# BinaryClock_LEDs.net
KiCad netlist of a schematic drawn in Altium Designer
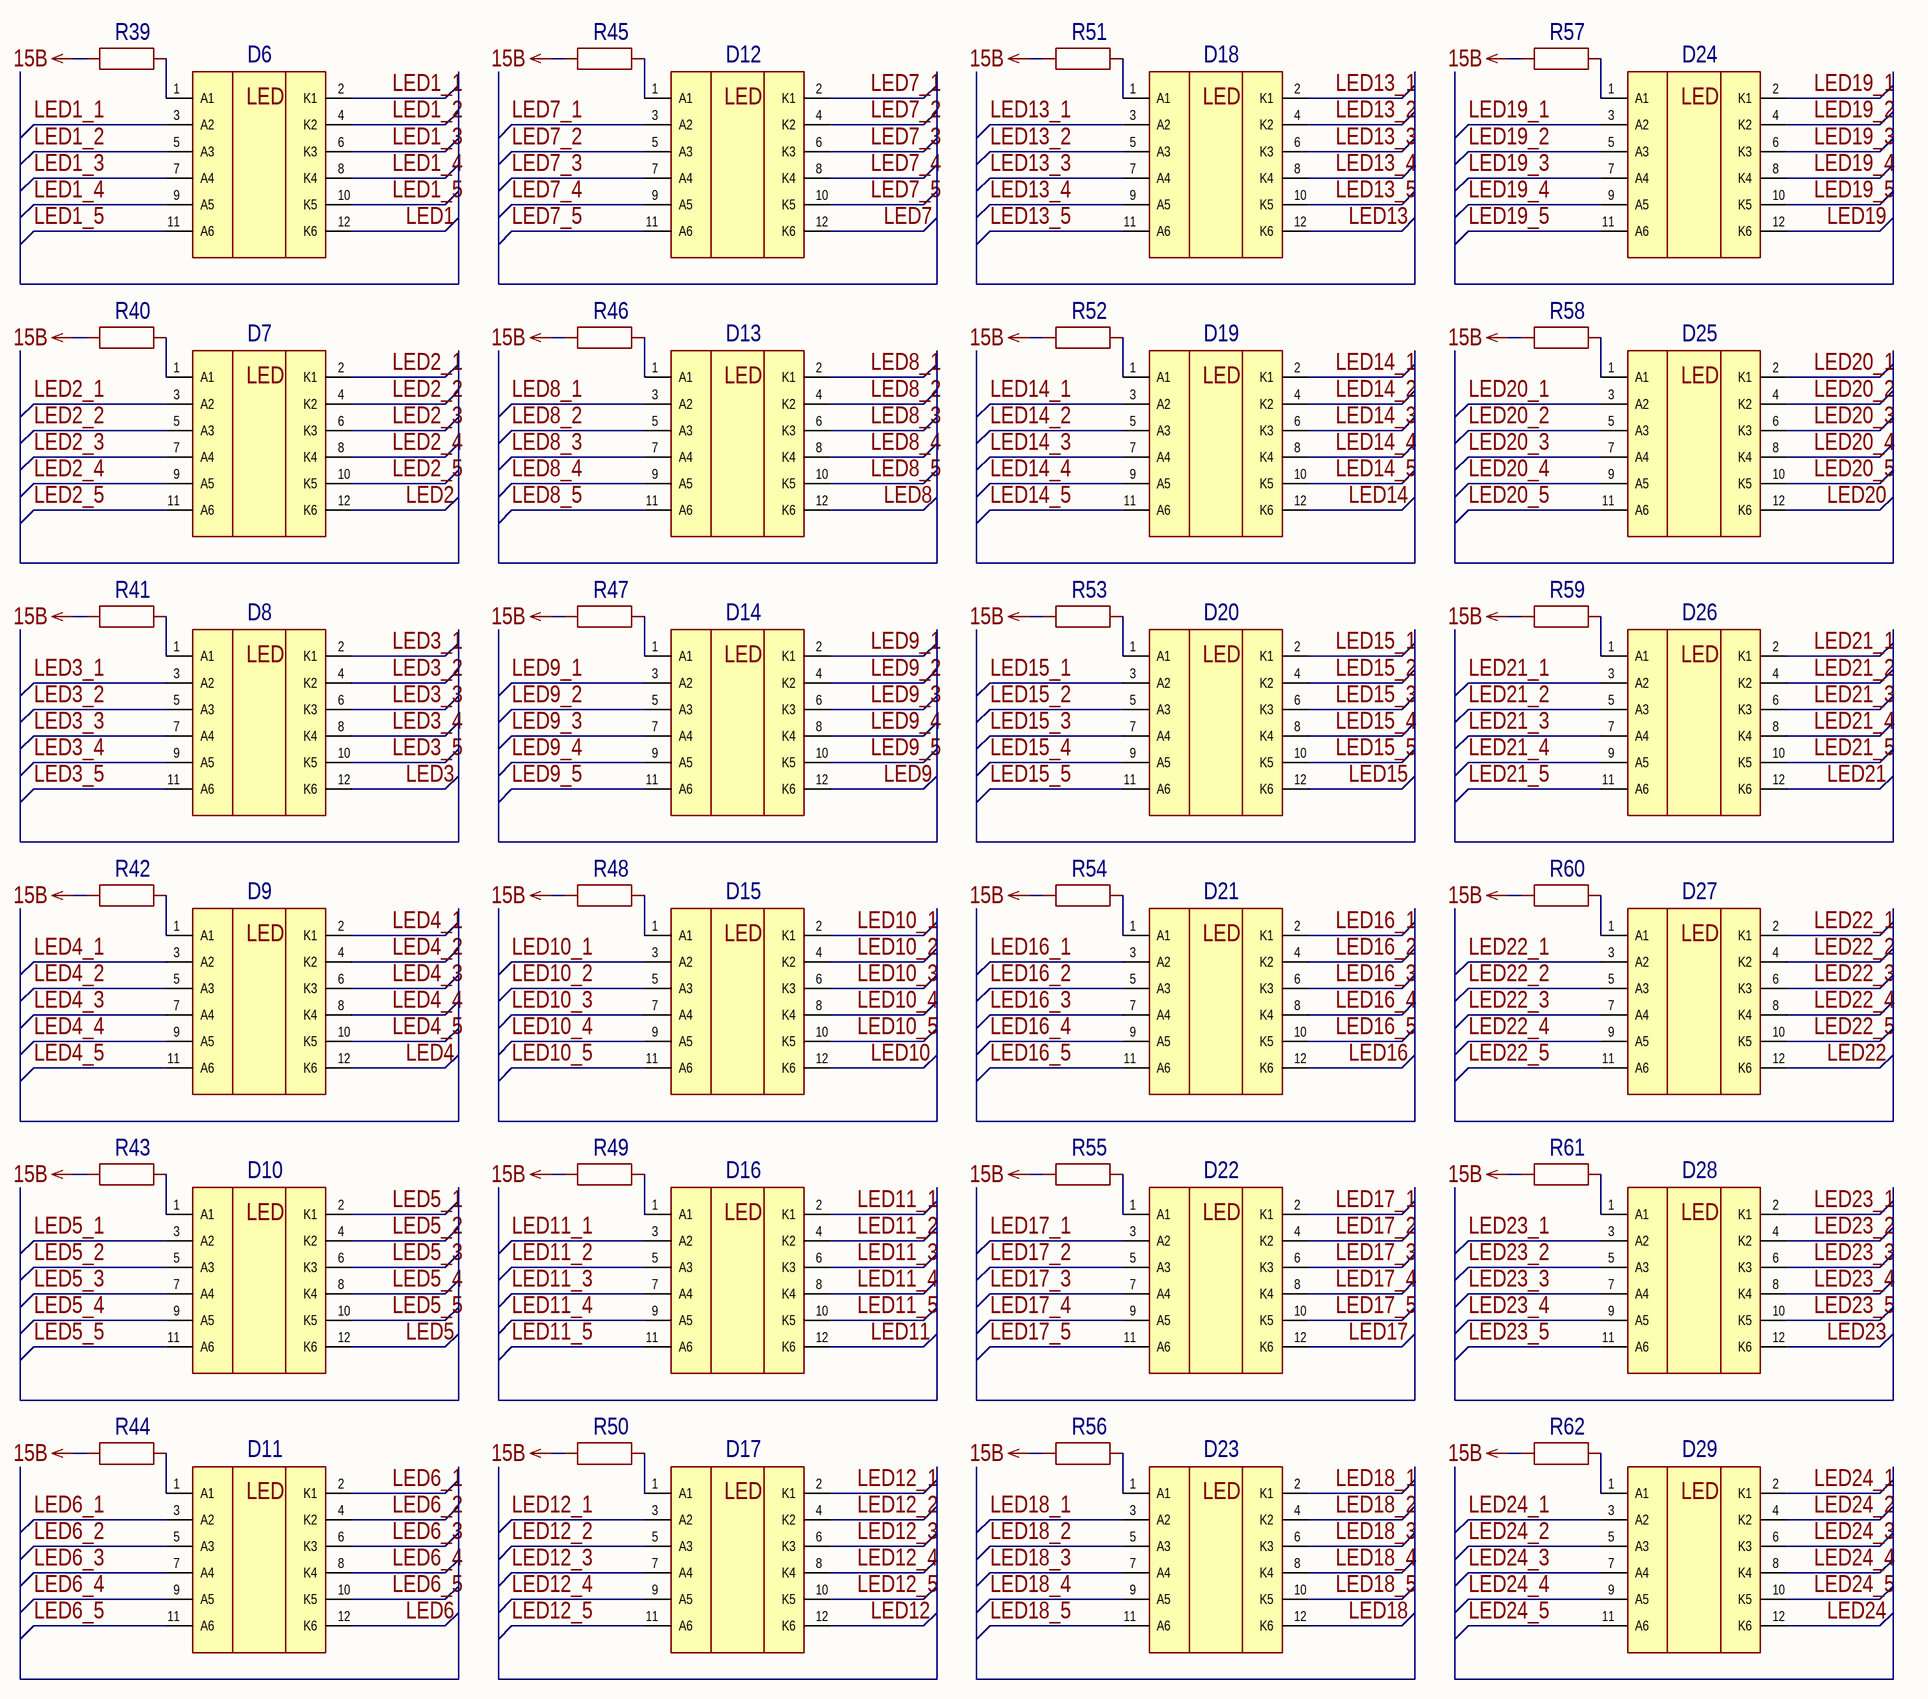
[diagram p0: BinaryClock_LEDs.SchDoc]

(export (version "E")
  (design (tool "Eeschema 10.0.6"))
  (components
    (comp (ref "D6")
      (value "DLA/6ID")
      (footprint "DLA/6ID")
      (description "20mm BIG LAMP")
      (fields (field (name "MANUFACTURER") "Kingbright"))
      (libsource (lib "Devices") (part "DLA"))
    )
    (comp (ref "D7")
      (value "DLA/6ID")
      (footprint "DLA/6ID")
      (description "20mm BIG LAMP")
      (fields (field (name "MANUFACTURER") "Kingbright"))
      (libsource (lib "Devices") (part "DLA"))
    )
    (comp (ref "D8")
      (value "DLA/6ID")
      (footprint "DLA/6ID")
      (description "20mm BIG LAMP")
      (fields (field (name "MANUFACTURER") "Kingbright"))
      (libsource (lib "Devices") (part "DLA"))
    )
    (comp (ref "D9")
      (value "DLA/6ID")
      (footprint "DLA/6ID")
      (description "20mm BIG LAMP")
      (fields (field (name "MANUFACTURER") "Kingbright"))
      (libsource (lib "Devices") (part "DLA"))
    )
    (comp (ref "D10")
      (value "DLA/6ID")
      (footprint "DLA/6ID")
      (description "20mm BIG LAMP")
      (fields (field (name "MANUFACTURER") "Kingbright"))
      (libsource (lib "Devices") (part "DLA"))
    )
    (comp (ref "D11")
      (value "DLA/6ID")
      (footprint "DLA/6ID")
      (description "20mm BIG LAMP")
      (fields (field (name "MANUFACTURER") "Kingbright"))
      (libsource (lib "Devices") (part "DLA"))
    )
    (comp (ref "D12")
      (value "DLA/6ID")
      (footprint "DLA/6ID")
      (description "20mm BIG LAMP")
      (fields (field (name "MANUFACTURER") "Kingbright"))
      (libsource (lib "Devices") (part "DLA"))
    )
    (comp (ref "D13")
      (value "DLA/6ID")
      (footprint "DLA/6ID")
      (description "20mm BIG LAMP")
      (fields (field (name "MANUFACTURER") "Kingbright"))
      (libsource (lib "Devices") (part "DLA"))
    )
    (comp (ref "D14")
      (value "DLA/6YD")
      (footprint "DLA/6YD")
      (description "20mm BIG LAMP")
      (fields (field (name "MANUFACTURER") "Kingbright"))
      (libsource (lib "Devices") (part "DLA"))
    )
    (comp (ref "D15")
      (value "DLA/6YD")
      (footprint "DLA/6YD")
      (description "20mm BIG LAMP")
      (fields (field (name "MANUFACTURER") "Kingbright"))
      (libsource (lib "Devices") (part "DLA"))
    )
    (comp (ref "D16")
      (value "DLA/6YD")
      (footprint "DLA/6YD")
      (description "20mm BIG LAMP")
      (fields (field (name "MANUFACTURER") "Kingbright"))
      (libsource (lib "Devices") (part "DLA"))
    )
    (comp (ref "D17")
      (value "DLA/6YD")
      (footprint "DLA/6YD")
      (description "20mm BIG LAMP")
      (fields (field (name "MANUFACTURER") "Kingbright"))
      (libsource (lib "Devices") (part "DLA"))
    )
    (comp (ref "D18")
      (value "DLA/6YD")
      (footprint "DLA/6YD")
      (description "20mm BIG LAMP")
      (fields (field (name "MANUFACTURER") "Kingbright"))
      (libsource (lib "Devices") (part "DLA"))
    )
    (comp (ref "D19")
      (value "DLA/6YD")
      (footprint "DLA/6YD")
      (description "20mm BIG LAMP")
      (fields (field (name "MANUFACTURER") "Kingbright"))
      (libsource (lib "Devices") (part "DLA"))
    )
    (comp (ref "D20")
      (value "DLA/6YD")
      (footprint "DLA/6YD")
      (description "20mm BIG LAMP")
      (fields (field (name "MANUFACTURER") "Kingbright"))
      (libsource (lib "Devices") (part "DLA"))
    )
    (comp (ref "D21")
      (value "DLA/6YD")
      (footprint "DLA/6YD")
      (description "20mm BIG LAMP")
      (fields (field (name "MANUFACTURER") "Kingbright"))
      (libsource (lib "Devices") (part "DLA"))
    )
    (comp (ref "D22")
      (value "DLA/6GD")
      (footprint "DLA/6GD")
      (description "20mm BIG LAMP")
      (fields (field (name "MANUFACTURER") "Kingbright"))
      (libsource (lib "Devices") (part "DLA"))
    )
    (comp (ref "D23")
      (value "DLA/6GD")
      (footprint "DLA/6GD")
      (description "20mm BIG LAMP")
      (fields (field (name "MANUFACTURER") "Kingbright"))
      (libsource (lib "Devices") (part "DLA"))
    )
    (comp (ref "D24")
      (value "DLA/6GD")
      (footprint "DLA/6GD")
      (description "20mm BIG LAMP")
      (fields (field (name "MANUFACTURER") "Kingbright"))
      (libsource (lib "Devices") (part "DLA"))
    )
    (comp (ref "D25")
      (value "DLA/6GD")
      (footprint "DLA/6GD")
      (description "20mm BIG LAMP")
      (fields (field (name "MANUFACTURER") "Kingbright"))
      (libsource (lib "Devices") (part "DLA"))
    )
    (comp (ref "D26")
      (value "DLA/6GD")
      (footprint "DLA/6GD")
      (description "20mm BIG LAMP")
      (fields (field (name "MANUFACTURER") "Kingbright"))
      (libsource (lib "Devices") (part "DLA"))
    )
    (comp (ref "D27")
      (value "DLA/6GD")
      (footprint "DLA/6GD")
      (description "20mm BIG LAMP")
      (fields (field (name "MANUFACTURER") "Kingbright"))
      (libsource (lib "Devices") (part "DLA"))
    )
    (comp (ref "D28")
      (value "DLA/6GD")
      (footprint "DLA/6GD")
      (description "20mm BIG LAMP")
      (fields (field (name "MANUFACTURER") "Kingbright"))
      (libsource (lib "Devices") (part "DLA"))
    )
    (comp (ref "D29")
      (value "DLA/6GD")
      (footprint "DLA/6GD")
      (description "20mm BIG LAMP")
      (fields (field (name "MANUFACTURER") "Kingbright"))
      (libsource (lib "Devices") (part "DLA"))
    )
    (comp (ref "R39")
      (value "0805±1 %-? кОм")
      (footprint "SMD-0805-RES")
      (description "Resistor")
      (libsource (lib "Passive,Diodes") (part "Res"))
    )
    (comp (ref "R40")
      (value "0805±1 %-? кОм")
      (footprint "SMD-0805-RES")
      (description "Resistor")
      (libsource (lib "Passive,Diodes") (part "Res"))
    )
    (comp (ref "R41")
      (value "0805±1 %-? кОм")
      (footprint "SMD-0805-RES")
      (description "Resistor")
      (libsource (lib "Passive,Diodes") (part "Res"))
    )
    (comp (ref "R42")
      (value "0805±1 %-? кОм")
      (footprint "SMD-0805-RES")
      (description "Resistor")
      (libsource (lib "Passive,Diodes") (part "Res"))
    )
    (comp (ref "R43")
      (value "0805±1 %-? кОм")
      (footprint "SMD-0805-RES")
      (description "Resistor")
      (libsource (lib "Passive,Diodes") (part "Res"))
    )
    (comp (ref "R44")
      (value "0805±1 %-? кОм")
      (footprint "SMD-0805-RES")
      (description "Resistor")
      (libsource (lib "Passive,Diodes") (part "Res"))
    )
    (comp (ref "R45")
      (value "0805±1 %-? кОм")
      (footprint "SMD-0805-RES")
      (description "Resistor")
      (libsource (lib "Passive,Diodes") (part "Res"))
    )
    (comp (ref "R46")
      (value "0805±1 %-? кОм")
      (footprint "SMD-0805-RES")
      (description "Resistor")
      (libsource (lib "Passive,Diodes") (part "Res"))
    )
    (comp (ref "R47")
      (value "0805±1 %-? кОм")
      (footprint "SMD-0805-RES")
      (description "Resistor")
      (libsource (lib "Passive,Diodes") (part "Res"))
    )
    (comp (ref "R48")
      (value "0805±1 %-? кОм")
      (footprint "SMD-0805-RES")
      (description "Resistor")
      (libsource (lib "Passive,Diodes") (part "Res"))
    )
    (comp (ref "R49")
      (value "0805±1 %-? кОм")
      (footprint "SMD-0805-RES")
      (description "Resistor")
      (libsource (lib "Passive,Diodes") (part "Res"))
    )
    (comp (ref "R50")
      (value "0805±1 %-? кОм")
      (footprint "SMD-0805-RES")
      (description "Resistor")
      (libsource (lib "Passive,Diodes") (part "Res"))
    )
    (comp (ref "R51")
      (value "0805±1 %-? кОм")
      (footprint "SMD-0805-RES")
      (description "Resistor")
      (libsource (lib "Passive,Diodes") (part "Res"))
    )
    (comp (ref "R52")
      (value "0805±1 %-? кОм")
      (footprint "SMD-0805-RES")
      (description "Resistor")
      (libsource (lib "Passive,Diodes") (part "Res"))
    )
    (comp (ref "R53")
      (value "0805±1 %-? кОм")
      (footprint "SMD-0805-RES")
      (description "Resistor")
      (libsource (lib "Passive,Diodes") (part "Res"))
    )
    (comp (ref "R54")
      (value "0805±1 %-? кОм")
      (footprint "SMD-0805-RES")
      (description "Resistor")
      (libsource (lib "Passive,Diodes") (part "Res"))
    )
    (comp (ref "R55")
      (value "0805±1 %-? кОм")
      (footprint "SMD-0805-RES")
      (description "Resistor")
      (libsource (lib "Passive,Diodes") (part "Res"))
    )
    (comp (ref "R56")
      (value "0805±1 %-? кОм")
      (footprint "SMD-0805-RES")
      (description "Resistor")
      (libsource (lib "Passive,Diodes") (part "Res"))
    )
    (comp (ref "R57")
      (value "0805±1 %-? кОм")
      (footprint "SMD-0805-RES")
      (description "Resistor")
      (libsource (lib "Passive,Diodes") (part "Res"))
    )
    (comp (ref "R58")
      (value "0805±1 %-? кОм")
      (footprint "SMD-0805-RES")
      (description "Resistor")
      (libsource (lib "Passive,Diodes") (part "Res"))
    )
    (comp (ref "R59")
      (value "0805±1 %-? кОм")
      (footprint "SMD-0805-RES")
      (description "Resistor")
      (libsource (lib "Passive,Diodes") (part "Res"))
    )
    (comp (ref "R60")
      (value "0805±1 %-? кОм")
      (footprint "SMD-0805-RES")
      (description "Resistor")
      (libsource (lib "Passive,Diodes") (part "Res"))
    )
    (comp (ref "R61")
      (value "0805±1 %-? кОм")
      (footprint "SMD-0805-RES")
      (description "Resistor")
      (libsource (lib "Passive,Diodes") (part "Res"))
    )
    (comp (ref "R62")
      (value "0805±1 %-? кОм")
      (footprint "SMD-0805-RES")
      (description "Resistor")
      (libsource (lib "Passive,Diodes") (part "Res"))
    )
  )
  (nets
    (net (code "1") (name "/LED1") (class "Default")
      (node (ref "D6") (pin "12") (pinfunction "K6_12") (pintype "passive"))
    )
    (net (code "2") (name "/LED1_1") (class "Default")
      (node (ref "D6") (pin "2") (pinfunction "K1_2") (pintype "passive"))
      (node (ref "D6") (pin "3") (pinfunction "A2_3") (pintype "passive"))
    )
    (net (code "3") (name "/LED1_2") (class "Default")
      (node (ref "D6") (pin "4") (pinfunction "K2_4") (pintype "passive"))
      (node (ref "D6") (pin "5") (pinfunction "A3_5") (pintype "passive"))
    )
    (net (code "4") (name "/LED1_3") (class "Default")
      (node (ref "D6") (pin "6") (pinfunction "K3_6") (pintype "passive"))
      (node (ref "D6") (pin "7") (pinfunction "A4_7") (pintype "passive"))
    )
    (net (code "5") (name "/LED1_4") (class "Default")
      (node (ref "D6") (pin "8") (pinfunction "K4_8") (pintype "passive"))
      (node (ref "D6") (pin "9") (pinfunction "A5_9") (pintype "passive"))
    )
    (net (code "6") (name "/LED1_5") (class "Default")
      (node (ref "D6") (pin "10") (pinfunction "K5_10") (pintype "passive"))
      (node (ref "D6") (pin "11") (pinfunction "A6_11") (pintype "passive"))
    )
    (net (code "7") (name "/LED2") (class "Default")
      (node (ref "D7") (pin "12") (pinfunction "K6_12") (pintype "passive"))
    )
    (net (code "8") (name "/LED2_1") (class "Default")
      (node (ref "D7") (pin "2") (pinfunction "K1_2") (pintype "passive"))
      (node (ref "D7") (pin "3") (pinfunction "A2_3") (pintype "passive"))
    )
    (net (code "9") (name "/LED2_2") (class "Default")
      (node (ref "D7") (pin "4") (pinfunction "K2_4") (pintype "passive"))
      (node (ref "D7") (pin "5") (pinfunction "A3_5") (pintype "passive"))
    )
    (net (code "10") (name "/LED2_3") (class "Default")
      (node (ref "D7") (pin "6") (pinfunction "K3_6") (pintype "passive"))
      (node (ref "D7") (pin "7") (pinfunction "A4_7") (pintype "passive"))
    )
    (net (code "11") (name "/LED2_4") (class "Default")
      (node (ref "D7") (pin "8") (pinfunction "K4_8") (pintype "passive"))
      (node (ref "D7") (pin "9") (pinfunction "A5_9") (pintype "passive"))
    )
    (net (code "12") (name "/LED2_5") (class "Default")
      (node (ref "D7") (pin "10") (pinfunction "K5_10") (pintype "passive"))
      (node (ref "D7") (pin "11") (pinfunction "A6_11") (pintype "passive"))
    )
    (net (code "13") (name "/LED3") (class "Default")
      (node (ref "D8") (pin "12") (pinfunction "K6_12") (pintype "passive"))
    )
    (net (code "14") (name "/LED3_1") (class "Default")
      (node (ref "D8") (pin "2") (pinfunction "K1_2") (pintype "passive"))
      (node (ref "D8") (pin "3") (pinfunction "A2_3") (pintype "passive"))
    )
    (net (code "15") (name "/LED3_2") (class "Default")
      (node (ref "D8") (pin "4") (pinfunction "K2_4") (pintype "passive"))
      (node (ref "D8") (pin "5") (pinfunction "A3_5") (pintype "passive"))
    )
    (net (code "16") (name "/LED3_3") (class "Default")
      (node (ref "D8") (pin "6") (pinfunction "K3_6") (pintype "passive"))
      (node (ref "D8") (pin "7") (pinfunction "A4_7") (pintype "passive"))
    )
    (net (code "17") (name "/LED3_4") (class "Default")
      (node (ref "D8") (pin "8") (pinfunction "K4_8") (pintype "passive"))
      (node (ref "D8") (pin "9") (pinfunction "A5_9") (pintype "passive"))
    )
    (net (code "18") (name "/LED3_5") (class "Default")
      (node (ref "D8") (pin "10") (pinfunction "K5_10") (pintype "passive"))
      (node (ref "D8") (pin "11") (pinfunction "A6_11") (pintype "passive"))
    )
    (net (code "19") (name "/LED4") (class "Default")
      (node (ref "D9") (pin "12") (pinfunction "K6_12") (pintype "passive"))
    )
    (net (code "20") (name "/LED4_1") (class "Default")
      (node (ref "D9") (pin "2") (pinfunction "K1_2") (pintype "passive"))
      (node (ref "D9") (pin "3") (pinfunction "A2_3") (pintype "passive"))
    )
    (net (code "21") (name "/LED4_2") (class "Default")
      (node (ref "D9") (pin "4") (pinfunction "K2_4") (pintype "passive"))
      (node (ref "D9") (pin "5") (pinfunction "A3_5") (pintype "passive"))
    )
    (net (code "22") (name "/LED4_3") (class "Default")
      (node (ref "D9") (pin "6") (pinfunction "K3_6") (pintype "passive"))
      (node (ref "D9") (pin "7") (pinfunction "A4_7") (pintype "passive"))
    )
    (net (code "23") (name "/LED4_4") (class "Default")
      (node (ref "D9") (pin "8") (pinfunction "K4_8") (pintype "passive"))
      (node (ref "D9") (pin "9") (pinfunction "A5_9") (pintype "passive"))
    )
    (net (code "24") (name "/LED4_5") (class "Default")
      (node (ref "D9") (pin "10") (pinfunction "K5_10") (pintype "passive"))
      (node (ref "D9") (pin "11") (pinfunction "A6_11") (pintype "passive"))
    )
    (net (code "25") (name "/LED5") (class "Default")
      (node (ref "D10") (pin "12") (pinfunction "K6_12") (pintype "passive"))
    )
    (net (code "26") (name "/LED5_1") (class "Default")
      (node (ref "D10") (pin "2") (pinfunction "K1_2") (pintype "passive"))
      (node (ref "D10") (pin "3") (pinfunction "A2_3") (pintype "passive"))
    )
    (net (code "27") (name "/LED5_2") (class "Default")
      (node (ref "D10") (pin "4") (pinfunction "K2_4") (pintype "passive"))
      (node (ref "D10") (pin "5") (pinfunction "A3_5") (pintype "passive"))
    )
    (net (code "28") (name "/LED5_3") (class "Default")
      (node (ref "D10") (pin "6") (pinfunction "K3_6") (pintype "passive"))
      (node (ref "D10") (pin "7") (pinfunction "A4_7") (pintype "passive"))
    )
    (net (code "29") (name "/LED5_4") (class "Default")
      (node (ref "D10") (pin "8") (pinfunction "K4_8") (pintype "passive"))
      (node (ref "D10") (pin "9") (pinfunction "A5_9") (pintype "passive"))
    )
    (net (code "30") (name "/LED5_5") (class "Default")
      (node (ref "D10") (pin "10") (pinfunction "K5_10") (pintype "passive"))
      (node (ref "D10") (pin "11") (pinfunction "A6_11") (pintype "passive"))
    )
    (net (code "31") (name "/LED6") (class "Default")
      (node (ref "D11") (pin "12") (pinfunction "K6_12") (pintype "passive"))
    )
    (net (code "32") (name "/LED6_1") (class "Default")
      (node (ref "D11") (pin "2") (pinfunction "K1_2") (pintype "passive"))
      (node (ref "D11") (pin "3") (pinfunction "A2_3") (pintype "passive"))
    )
    (net (code "33") (name "/LED6_2") (class "Default")
      (node (ref "D11") (pin "4") (pinfunction "K2_4") (pintype "passive"))
      (node (ref "D11") (pin "5") (pinfunction "A3_5") (pintype "passive"))
    )
    (net (code "34") (name "/LED6_3") (class "Default")
      (node (ref "D11") (pin "6") (pinfunction "K3_6") (pintype "passive"))
      (node (ref "D11") (pin "7") (pinfunction "A4_7") (pintype "passive"))
    )
    (net (code "35") (name "/LED6_4") (class "Default")
      (node (ref "D11") (pin "8") (pinfunction "K4_8") (pintype "passive"))
      (node (ref "D11") (pin "9") (pinfunction "A5_9") (pintype "passive"))
    )
    (net (code "36") (name "/LED6_5") (class "Default")
      (node (ref "D11") (pin "10") (pinfunction "K5_10") (pintype "passive"))
      (node (ref "D11") (pin "11") (pinfunction "A6_11") (pintype "passive"))
    )
    (net (code "37") (name "/LED7") (class "Default")
      (node (ref "D12") (pin "12") (pinfunction "K6_12") (pintype "passive"))
    )
    (net (code "38") (name "/LED7_1") (class "Default")
      (node (ref "D12") (pin "2") (pinfunction "K1_2") (pintype "passive"))
      (node (ref "D12") (pin "3") (pinfunction "A2_3") (pintype "passive"))
    )
    (net (code "39") (name "/LED7_2") (class "Default")
      (node (ref "D12") (pin "4") (pinfunction "K2_4") (pintype "passive"))
      (node (ref "D12") (pin "5") (pinfunction "A3_5") (pintype "passive"))
    )
    (net (code "40") (name "/LED7_3") (class "Default")
      (node (ref "D12") (pin "6") (pinfunction "K3_6") (pintype "passive"))
      (node (ref "D12") (pin "7") (pinfunction "A4_7") (pintype "passive"))
    )
    (net (code "41") (name "/LED7_4") (class "Default")
      (node (ref "D12") (pin "8") (pinfunction "K4_8") (pintype "passive"))
      (node (ref "D12") (pin "9") (pinfunction "A5_9") (pintype "passive"))
    )
    (net (code "42") (name "/LED7_5") (class "Default")
      (node (ref "D12") (pin "10") (pinfunction "K5_10") (pintype "passive"))
      (node (ref "D12") (pin "11") (pinfunction "A6_11") (pintype "passive"))
    )
    (net (code "43") (name "/LED8") (class "Default")
      (node (ref "D13") (pin "12") (pinfunction "K6_12") (pintype "passive"))
    )
    (net (code "44") (name "/LED8_1") (class "Default")
      (node (ref "D13") (pin "2") (pinfunction "K1_2") (pintype "passive"))
      (node (ref "D13") (pin "3") (pinfunction "A2_3") (pintype "passive"))
    )
    (net (code "45") (name "/LED8_2") (class "Default")
      (node (ref "D13") (pin "4") (pinfunction "K2_4") (pintype "passive"))
      (node (ref "D13") (pin "5") (pinfunction "A3_5") (pintype "passive"))
    )
    (net (code "46") (name "/LED8_3") (class "Default")
      (node (ref "D13") (pin "6") (pinfunction "K3_6") (pintype "passive"))
      (node (ref "D13") (pin "7") (pinfunction "A4_7") (pintype "passive"))
    )
    (net (code "47") (name "/LED8_4") (class "Default")
      (node (ref "D13") (pin "8") (pinfunction "K4_8") (pintype "passive"))
      (node (ref "D13") (pin "9") (pinfunction "A5_9") (pintype "passive"))
    )
    (net (code "48") (name "/LED8_5") (class "Default")
      (node (ref "D13") (pin "10") (pinfunction "K5_10") (pintype "passive"))
      (node (ref "D13") (pin "11") (pinfunction "A6_11") (pintype "passive"))
    )
    (net (code "49") (name "/LED9") (class "Default")
      (node (ref "D14") (pin "12") (pinfunction "K6_12") (pintype "passive"))
    )
    (net (code "50") (name "/LED9_1") (class "Default")
      (node (ref "D14") (pin "2") (pinfunction "K1_2") (pintype "passive"))
      (node (ref "D14") (pin "3") (pinfunction "A2_3") (pintype "passive"))
    )
    (net (code "51") (name "/LED9_2") (class "Default")
      (node (ref "D14") (pin "4") (pinfunction "K2_4") (pintype "passive"))
      (node (ref "D14") (pin "5") (pinfunction "A3_5") (pintype "passive"))
    )
    (net (code "52") (name "/LED9_3") (class "Default")
      (node (ref "D14") (pin "6") (pinfunction "K3_6") (pintype "passive"))
      (node (ref "D14") (pin "7") (pinfunction "A4_7") (pintype "passive"))
    )
    (net (code "53") (name "/LED9_4") (class "Default")
      (node (ref "D14") (pin "8") (pinfunction "K4_8") (pintype "passive"))
      (node (ref "D14") (pin "9") (pinfunction "A5_9") (pintype "passive"))
    )
    (net (code "54") (name "/LED9_5") (class "Default")
      (node (ref "D14") (pin "10") (pinfunction "K5_10") (pintype "passive"))
      (node (ref "D14") (pin "11") (pinfunction "A6_11") (pintype "passive"))
    )
    (net (code "55") (name "/LED10") (class "Default")
      (node (ref "D15") (pin "12") (pinfunction "K6_12") (pintype "passive"))
    )
    (net (code "56") (name "/LED10_1") (class "Default")
      (node (ref "D15") (pin "2") (pinfunction "K1_2") (pintype "passive"))
      (node (ref "D15") (pin "3") (pinfunction "A2_3") (pintype "passive"))
    )
    (net (code "57") (name "/LED10_2") (class "Default")
      (node (ref "D15") (pin "4") (pinfunction "K2_4") (pintype "passive"))
      (node (ref "D15") (pin "5") (pinfunction "A3_5") (pintype "passive"))
    )
    (net (code "58") (name "/LED10_3") (class "Default")
      (node (ref "D15") (pin "6") (pinfunction "K3_6") (pintype "passive"))
      (node (ref "D15") (pin "7") (pinfunction "A4_7") (pintype "passive"))
    )
    (net (code "59") (name "/LED10_4") (class "Default")
      (node (ref "D15") (pin "8") (pinfunction "K4_8") (pintype "passive"))
      (node (ref "D15") (pin "9") (pinfunction "A5_9") (pintype "passive"))
    )
    (net (code "60") (name "/LED10_5") (class "Default")
      (node (ref "D15") (pin "10") (pinfunction "K5_10") (pintype "passive"))
      (node (ref "D15") (pin "11") (pinfunction "A6_11") (pintype "passive"))
    )
    (net (code "61") (name "/LED11") (class "Default")
      (node (ref "D16") (pin "12") (pinfunction "K6_12") (pintype "passive"))
    )
    (net (code "62") (name "/LED11_1") (class "Default")
      (node (ref "D16") (pin "2") (pinfunction "K1_2") (pintype "passive"))
      (node (ref "D16") (pin "3") (pinfunction "A2_3") (pintype "passive"))
    )
    (net (code "63") (name "/LED11_2") (class "Default")
      (node (ref "D16") (pin "4") (pinfunction "K2_4") (pintype "passive"))
      (node (ref "D16") (pin "5") (pinfunction "A3_5") (pintype "passive"))
    )
    (net (code "64") (name "/LED11_3") (class "Default")
      (node (ref "D16") (pin "6") (pinfunction "K3_6") (pintype "passive"))
      (node (ref "D16") (pin "7") (pinfunction "A4_7") (pintype "passive"))
    )
    (net (code "65") (name "/LED11_4") (class "Default")
      (node (ref "D16") (pin "8") (pinfunction "K4_8") (pintype "passive"))
      (node (ref "D16") (pin "9") (pinfunction "A5_9") (pintype "passive"))
    )
    (net (code "66") (name "/LED11_5") (class "Default")
      (node (ref "D16") (pin "10") (pinfunction "K5_10") (pintype "passive"))
      (node (ref "D16") (pin "11") (pinfunction "A6_11") (pintype "passive"))
    )
    (net (code "67") (name "/LED12") (class "Default")
      (node (ref "D17") (pin "12") (pinfunction "K6_12") (pintype "passive"))
    )
    (net (code "68") (name "/LED12_1") (class "Default")
      (node (ref "D17") (pin "2") (pinfunction "K1_2") (pintype "passive"))
      (node (ref "D17") (pin "3") (pinfunction "A2_3") (pintype "passive"))
    )
    (net (code "69") (name "/LED12_2") (class "Default")
      (node (ref "D17") (pin "4") (pinfunction "K2_4") (pintype "passive"))
      (node (ref "D17") (pin "5") (pinfunction "A3_5") (pintype "passive"))
    )
    (net (code "70") (name "/LED12_3") (class "Default")
      (node (ref "D17") (pin "6") (pinfunction "K3_6") (pintype "passive"))
      (node (ref "D17") (pin "7") (pinfunction "A4_7") (pintype "passive"))
    )
    (net (code "71") (name "/LED12_4") (class "Default")
      (node (ref "D17") (pin "8") (pinfunction "K4_8") (pintype "passive"))
      (node (ref "D17") (pin "9") (pinfunction "A5_9") (pintype "passive"))
    )
    (net (code "72") (name "/LED12_5") (class "Default")
      (node (ref "D17") (pin "10") (pinfunction "K5_10") (pintype "passive"))
      (node (ref "D17") (pin "11") (pinfunction "A6_11") (pintype "passive"))
    )
    (net (code "73") (name "/LED13") (class "Default")
      (node (ref "D18") (pin "12") (pinfunction "K6_12") (pintype "passive"))
    )
    (net (code "74") (name "/LED13_1") (class "Default")
      (node (ref "D18") (pin "2") (pinfunction "K1_2") (pintype "passive"))
      (node (ref "D18") (pin "3") (pinfunction "A2_3") (pintype "passive"))
    )
    (net (code "75") (name "/LED13_2") (class "Default")
      (node (ref "D18") (pin "4") (pinfunction "K2_4") (pintype "passive"))
      (node (ref "D18") (pin "5") (pinfunction "A3_5") (pintype "passive"))
    )
    (net (code "76") (name "/LED13_3") (class "Default")
      (node (ref "D18") (pin "6") (pinfunction "K3_6") (pintype "passive"))
      (node (ref "D18") (pin "7") (pinfunction "A4_7") (pintype "passive"))
    )
    (net (code "77") (name "/LED13_4") (class "Default")
      (node (ref "D18") (pin "8") (pinfunction "K4_8") (pintype "passive"))
      (node (ref "D18") (pin "9") (pinfunction "A5_9") (pintype "passive"))
    )
    (net (code "78") (name "/LED13_5") (class "Default")
      (node (ref "D18") (pin "10") (pinfunction "K5_10") (pintype "passive"))
      (node (ref "D18") (pin "11") (pinfunction "A6_11") (pintype "passive"))
    )
    (net (code "79") (name "/LED14") (class "Default")
      (node (ref "D19") (pin "12") (pinfunction "K6_12") (pintype "passive"))
    )
    (net (code "80") (name "/LED14_1") (class "Default")
      (node (ref "D19") (pin "2") (pinfunction "K1_2") (pintype "passive"))
      (node (ref "D19") (pin "3") (pinfunction "A2_3") (pintype "passive"))
    )
    (net (code "81") (name "/LED14_2") (class "Default")
      (node (ref "D19") (pin "4") (pinfunction "K2_4") (pintype "passive"))
      (node (ref "D19") (pin "5") (pinfunction "A3_5") (pintype "passive"))
    )
    (net (code "82") (name "/LED14_3") (class "Default")
      (node (ref "D19") (pin "6") (pinfunction "K3_6") (pintype "passive"))
      (node (ref "D19") (pin "7") (pinfunction "A4_7") (pintype "passive"))
    )
    (net (code "83") (name "/LED14_4") (class "Default")
      (node (ref "D19") (pin "8") (pinfunction "K4_8") (pintype "passive"))
      (node (ref "D19") (pin "9") (pinfunction "A5_9") (pintype "passive"))
    )
    (net (code "84") (name "/LED14_5") (class "Default")
      (node (ref "D19") (pin "10") (pinfunction "K5_10") (pintype "passive"))
      (node (ref "D19") (pin "11") (pinfunction "A6_11") (pintype "passive"))
    )
    (net (code "85") (name "/LED15") (class "Default")
      (node (ref "D20") (pin "12") (pinfunction "K6_12") (pintype "passive"))
    )
    (net (code "86") (name "/LED15_1") (class "Default")
      (node (ref "D20") (pin "2") (pinfunction "K1_2") (pintype "passive"))
      (node (ref "D20") (pin "3") (pinfunction "A2_3") (pintype "passive"))
    )
    (net (code "87") (name "/LED15_2") (class "Default")
      (node (ref "D20") (pin "4") (pinfunction "K2_4") (pintype "passive"))
      (node (ref "D20") (pin "5") (pinfunction "A3_5") (pintype "passive"))
    )
    (net (code "88") (name "/LED15_3") (class "Default")
      (node (ref "D20") (pin "6") (pinfunction "K3_6") (pintype "passive"))
      (node (ref "D20") (pin "7") (pinfunction "A4_7") (pintype "passive"))
    )
    (net (code "89") (name "/LED15_4") (class "Default")
      (node (ref "D20") (pin "8") (pinfunction "K4_8") (pintype "passive"))
      (node (ref "D20") (pin "9") (pinfunction "A5_9") (pintype "passive"))
    )
    (net (code "90") (name "/LED15_5") (class "Default")
      (node (ref "D20") (pin "10") (pinfunction "K5_10") (pintype "passive"))
      (node (ref "D20") (pin "11") (pinfunction "A6_11") (pintype "passive"))
    )
    (net (code "91") (name "/LED16") (class "Default")
      (node (ref "D21") (pin "12") (pinfunction "K6_12") (pintype "passive"))
    )
    (net (code "92") (name "/LED16_1") (class "Default")
      (node (ref "D21") (pin "2") (pinfunction "K1_2") (pintype "passive"))
      (node (ref "D21") (pin "3") (pinfunction "A2_3") (pintype "passive"))
    )
    (net (code "93") (name "/LED16_2") (class "Default")
      (node (ref "D21") (pin "4") (pinfunction "K2_4") (pintype "passive"))
      (node (ref "D21") (pin "5") (pinfunction "A3_5") (pintype "passive"))
    )
    (net (code "94") (name "/LED16_3") (class "Default")
      (node (ref "D21") (pin "6") (pinfunction "K3_6") (pintype "passive"))
      (node (ref "D21") (pin "7") (pinfunction "A4_7") (pintype "passive"))
    )
    (net (code "95") (name "/LED16_4") (class "Default")
      (node (ref "D21") (pin "8") (pinfunction "K4_8") (pintype "passive"))
      (node (ref "D21") (pin "9") (pinfunction "A5_9") (pintype "passive"))
    )
    (net (code "96") (name "/LED16_5") (class "Default")
      (node (ref "D21") (pin "10") (pinfunction "K5_10") (pintype "passive"))
      (node (ref "D21") (pin "11") (pinfunction "A6_11") (pintype "passive"))
    )
    (net (code "97") (name "/LED17") (class "Default")
      (node (ref "D22") (pin "12") (pinfunction "K6_12") (pintype "passive"))
    )
    (net (code "98") (name "/LED17_1") (class "Default")
      (node (ref "D22") (pin "2") (pinfunction "K1_2") (pintype "passive"))
      (node (ref "D22") (pin "3") (pinfunction "A2_3") (pintype "passive"))
    )
    (net (code "99") (name "/LED17_2") (class "Default")
      (node (ref "D22") (pin "4") (pinfunction "K2_4") (pintype "passive"))
      (node (ref "D22") (pin "5") (pinfunction "A3_5") (pintype "passive"))
    )
    (net (code "100") (name "/LED17_3") (class "Default")
      (node (ref "D22") (pin "6") (pinfunction "K3_6") (pintype "passive"))
      (node (ref "D22") (pin "7") (pinfunction "A4_7") (pintype "passive"))
    )
    (net (code "101") (name "/LED17_4") (class "Default")
      (node (ref "D22") (pin "8") (pinfunction "K4_8") (pintype "passive"))
      (node (ref "D22") (pin "9") (pinfunction "A5_9") (pintype "passive"))
    )
    (net (code "102") (name "/LED17_5") (class "Default")
      (node (ref "D22") (pin "10") (pinfunction "K5_10") (pintype "passive"))
      (node (ref "D22") (pin "11") (pinfunction "A6_11") (pintype "passive"))
    )
    (net (code "103") (name "/LED18") (class "Default")
      (node (ref "D23") (pin "12") (pinfunction "K6_12") (pintype "passive"))
    )
    (net (code "104") (name "/LED18_1") (class "Default")
      (node (ref "D23") (pin "2") (pinfunction "K1_2") (pintype "passive"))
      (node (ref "D23") (pin "3") (pinfunction "A2_3") (pintype "passive"))
    )
    (net (code "105") (name "/LED18_2") (class "Default")
      (node (ref "D23") (pin "4") (pinfunction "K2_4") (pintype "passive"))
      (node (ref "D23") (pin "5") (pinfunction "A3_5") (pintype "passive"))
    )
    (net (code "106") (name "/LED18_3") (class "Default")
      (node (ref "D23") (pin "6") (pinfunction "K3_6") (pintype "passive"))
      (node (ref "D23") (pin "7") (pinfunction "A4_7") (pintype "passive"))
    )
    (net (code "107") (name "/LED18_4") (class "Default")
      (node (ref "D23") (pin "8") (pinfunction "K4_8") (pintype "passive"))
      (node (ref "D23") (pin "9") (pinfunction "A5_9") (pintype "passive"))
    )
    (net (code "108") (name "/LED18_5") (class "Default")
      (node (ref "D23") (pin "10") (pinfunction "K5_10") (pintype "passive"))
      (node (ref "D23") (pin "11") (pinfunction "A6_11") (pintype "passive"))
    )
    (net (code "109") (name "/LED19") (class "Default")
      (node (ref "D24") (pin "12") (pinfunction "K6_12") (pintype "passive"))
    )
    (net (code "110") (name "/LED19_1") (class "Default")
      (node (ref "D24") (pin "2") (pinfunction "K1_2") (pintype "passive"))
      (node (ref "D24") (pin "3") (pinfunction "A2_3") (pintype "passive"))
    )
    (net (code "111") (name "/LED19_2") (class "Default")
      (node (ref "D24") (pin "4") (pinfunction "K2_4") (pintype "passive"))
      (node (ref "D24") (pin "5") (pinfunction "A3_5") (pintype "passive"))
    )
    (net (code "112") (name "/LED19_3") (class "Default")
      (node (ref "D24") (pin "6") (pinfunction "K3_6") (pintype "passive"))
      (node (ref "D24") (pin "7") (pinfunction "A4_7") (pintype "passive"))
    )
    (net (code "113") (name "/LED19_4") (class "Default")
      (node (ref "D24") (pin "8") (pinfunction "K4_8") (pintype "passive"))
      (node (ref "D24") (pin "9") (pinfunction "A5_9") (pintype "passive"))
    )
    (net (code "114") (name "/LED19_5") (class "Default")
      (node (ref "D24") (pin "10") (pinfunction "K5_10") (pintype "passive"))
      (node (ref "D24") (pin "11") (pinfunction "A6_11") (pintype "passive"))
    )
    (net (code "115") (name "/LED20") (class "Default")
      (node (ref "D25") (pin "12") (pinfunction "K6_12") (pintype "passive"))
    )
    (net (code "116") (name "/LED20_1") (class "Default")
      (node (ref "D25") (pin "2") (pinfunction "K1_2") (pintype "passive"))
      (node (ref "D25") (pin "3") (pinfunction "A2_3") (pintype "passive"))
    )
    (net (code "117") (name "/LED20_2") (class "Default")
      (node (ref "D25") (pin "4") (pinfunction "K2_4") (pintype "passive"))
      (node (ref "D25") (pin "5") (pinfunction "A3_5") (pintype "passive"))
    )
    (net (code "118") (name "/LED20_3") (class "Default")
      (node (ref "D25") (pin "6") (pinfunction "K3_6") (pintype "passive"))
      (node (ref "D25") (pin "7") (pinfunction "A4_7") (pintype "passive"))
    )
    (net (code "119") (name "/LED20_4") (class "Default")
      (node (ref "D25") (pin "8") (pinfunction "K4_8") (pintype "passive"))
      (node (ref "D25") (pin "9") (pinfunction "A5_9") (pintype "passive"))
    )
    (net (code "120") (name "/LED20_5") (class "Default")
      (node (ref "D25") (pin "10") (pinfunction "K5_10") (pintype "passive"))
      (node (ref "D25") (pin "11") (pinfunction "A6_11") (pintype "passive"))
    )
    (net (code "121") (name "/LED21") (class "Default")
      (node (ref "D26") (pin "12") (pinfunction "K6_12") (pintype "passive"))
    )
    (net (code "122") (name "/LED21_1") (class "Default")
      (node (ref "D26") (pin "2") (pinfunction "K1_2") (pintype "passive"))
      (node (ref "D26") (pin "3") (pinfunction "A2_3") (pintype "passive"))
    )
    (net (code "123") (name "/LED21_2") (class "Default")
      (node (ref "D26") (pin "4") (pinfunction "K2_4") (pintype "passive"))
      (node (ref "D26") (pin "5") (pinfunction "A3_5") (pintype "passive"))
    )
    (net (code "124") (name "/LED21_3") (class "Default")
      (node (ref "D26") (pin "6") (pinfunction "K3_6") (pintype "passive"))
      (node (ref "D26") (pin "7") (pinfunction "A4_7") (pintype "passive"))
    )
    (net (code "125") (name "/LED21_4") (class "Default")
      (node (ref "D26") (pin "8") (pinfunction "K4_8") (pintype "passive"))
      (node (ref "D26") (pin "9") (pinfunction "A5_9") (pintype "passive"))
    )
    (net (code "126") (name "/LED21_5") (class "Default")
      (node (ref "D26") (pin "10") (pinfunction "K5_10") (pintype "passive"))
      (node (ref "D26") (pin "11") (pinfunction "A6_11") (pintype "passive"))
    )
    (net (code "127") (name "/LED22") (class "Default")
      (node (ref "D27") (pin "12") (pinfunction "K6_12") (pintype "passive"))
    )
    (net (code "128") (name "/LED22_1") (class "Default")
      (node (ref "D27") (pin "2") (pinfunction "K1_2") (pintype "passive"))
      (node (ref "D27") (pin "3") (pinfunction "A2_3") (pintype "passive"))
    )
    (net (code "129") (name "/LED22_2") (class "Default")
      (node (ref "D27") (pin "4") (pinfunction "K2_4") (pintype "passive"))
      (node (ref "D27") (pin "5") (pinfunction "A3_5") (pintype "passive"))
    )
    (net (code "130") (name "/LED22_3") (class "Default")
      (node (ref "D27") (pin "6") (pinfunction "K3_6") (pintype "passive"))
      (node (ref "D27") (pin "7") (pinfunction "A4_7") (pintype "passive"))
    )
    (net (code "131") (name "/LED22_4") (class "Default")
      (node (ref "D27") (pin "8") (pinfunction "K4_8") (pintype "passive"))
      (node (ref "D27") (pin "9") (pinfunction "A5_9") (pintype "passive"))
    )
    (net (code "132") (name "/LED22_5") (class "Default")
      (node (ref "D27") (pin "10") (pinfunction "K5_10") (pintype "passive"))
      (node (ref "D27") (pin "11") (pinfunction "A6_11") (pintype "passive"))
    )
    (net (code "133") (name "/LED23") (class "Default")
      (node (ref "D28") (pin "12") (pinfunction "K6_12") (pintype "passive"))
    )
    (net (code "134") (name "/LED23_1") (class "Default")
      (node (ref "D28") (pin "2") (pinfunction "K1_2") (pintype "passive"))
      (node (ref "D28") (pin "3") (pinfunction "A2_3") (pintype "passive"))
    )
    (net (code "135") (name "/LED23_2") (class "Default")
      (node (ref "D28") (pin "4") (pinfunction "K2_4") (pintype "passive"))
      (node (ref "D28") (pin "5") (pinfunction "A3_5") (pintype "passive"))
    )
    (net (code "136") (name "/LED23_3") (class "Default")
      (node (ref "D28") (pin "6") (pinfunction "K3_6") (pintype "passive"))
      (node (ref "D28") (pin "7") (pinfunction "A4_7") (pintype "passive"))
    )
    (net (code "137") (name "/LED23_4") (class "Default")
      (node (ref "D28") (pin "8") (pinfunction "K4_8") (pintype "passive"))
      (node (ref "D28") (pin "9") (pinfunction "A5_9") (pintype "passive"))
    )
    (net (code "138") (name "/LED23_5") (class "Default")
      (node (ref "D28") (pin "10") (pinfunction "K5_10") (pintype "passive"))
      (node (ref "D28") (pin "11") (pinfunction "A6_11") (pintype "passive"))
    )
    (net (code "139") (name "/LED24") (class "Default")
      (node (ref "D29") (pin "12") (pinfunction "K6_12") (pintype "passive"))
    )
    (net (code "140") (name "/LED24_1") (class "Default")
      (node (ref "D29") (pin "2") (pinfunction "K1_2") (pintype "passive"))
      (node (ref "D29") (pin "3") (pinfunction "A2_3") (pintype "passive"))
    )
    (net (code "141") (name "/LED24_2") (class "Default")
      (node (ref "D29") (pin "4") (pinfunction "K2_4") (pintype "passive"))
      (node (ref "D29") (pin "5") (pinfunction "A3_5") (pintype "passive"))
    )
    (net (code "142") (name "/LED24_3") (class "Default")
      (node (ref "D29") (pin "6") (pinfunction "K3_6") (pintype "passive"))
      (node (ref "D29") (pin "7") (pinfunction "A4_7") (pintype "passive"))
    )
    (net (code "143") (name "/LED24_4") (class "Default")
      (node (ref "D29") (pin "8") (pinfunction "K4_8") (pintype "passive"))
      (node (ref "D29") (pin "9") (pinfunction "A5_9") (pintype "passive"))
    )
    (net (code "144") (name "/LED24_5") (class "Default")
      (node (ref "D29") (pin "10") (pinfunction "K5_10") (pintype "passive"))
      (node (ref "D29") (pin "11") (pinfunction "A6_11") (pintype "passive"))
    )
    (net (code "145") (name "15В") (class "Default")
      (node (ref "R39") (pin "1") (pinfunction "1_1") (pintype "passive"))
      (node (ref "R40") (pin "1") (pinfunction "1_1") (pintype "passive"))
      (node (ref "R41") (pin "1") (pinfunction "1_1") (pintype "passive"))
      (node (ref "R42") (pin "1") (pinfunction "1_1") (pintype "passive"))
      (node (ref "R43") (pin "1") (pinfunction "1_1") (pintype "passive"))
      (node (ref "R44") (pin "1") (pinfunction "1_1") (pintype "passive"))
      (node (ref "R45") (pin "1") (pinfunction "1_1") (pintype "passive"))
      (node (ref "R46") (pin "1") (pinfunction "1_1") (pintype "passive"))
      (node (ref "R47") (pin "1") (pinfunction "1_1") (pintype "passive"))
      (node (ref "R48") (pin "1") (pinfunction "1_1") (pintype "passive"))
      (node (ref "R49") (pin "1") (pinfunction "1_1") (pintype "passive"))
      (node (ref "R50") (pin "1") (pinfunction "1_1") (pintype "passive"))
      (node (ref "R51") (pin "1") (pinfunction "1_1") (pintype "passive"))
      (node (ref "R52") (pin "1") (pinfunction "1_1") (pintype "passive"))
      (node (ref "R53") (pin "1") (pinfunction "1_1") (pintype "passive"))
      (node (ref "R54") (pin "1") (pinfunction "1_1") (pintype "passive"))
      (node (ref "R55") (pin "1") (pinfunction "1_1") (pintype "passive"))
      (node (ref "R56") (pin "1") (pinfunction "1_1") (pintype "passive"))
      (node (ref "R57") (pin "1") (pinfunction "1_1") (pintype "passive"))
      (node (ref "R58") (pin "1") (pinfunction "1_1") (pintype "passive"))
      (node (ref "R59") (pin "1") (pinfunction "1_1") (pintype "passive"))
      (node (ref "R60") (pin "1") (pinfunction "1_1") (pintype "passive"))
      (node (ref "R61") (pin "1") (pinfunction "1_1") (pintype "passive"))
      (node (ref "R62") (pin "1") (pinfunction "1_1") (pintype "passive"))
    )
    (net (code "146") (name "Net-(D6-A1)") (class "Default")
      (node (ref "D6") (pin "1") (pinfunction "A1_1") (pintype "passive"))
      (node (ref "R39") (pin "2") (pinfunction "2_2") (pintype "passive"))
    )
    (net (code "147") (name "Net-(D7-A1)") (class "Default")
      (node (ref "D7") (pin "1") (pinfunction "A1_1") (pintype "passive"))
      (node (ref "R40") (pin "2") (pinfunction "2_2") (pintype "passive"))
    )
    (net (code "148") (name "Net-(D8-A1)") (class "Default")
      (node (ref "D8") (pin "1") (pinfunction "A1_1") (pintype "passive"))
      (node (ref "R41") (pin "2") (pinfunction "2_2") (pintype "passive"))
    )
    (net (code "149") (name "Net-(D9-A1)") (class "Default")
      (node (ref "D9") (pin "1") (pinfunction "A1_1") (pintype "passive"))
      (node (ref "R42") (pin "2") (pinfunction "2_2") (pintype "passive"))
    )
    (net (code "150") (name "Net-(D10-A1)") (class "Default")
      (node (ref "D10") (pin "1") (pinfunction "A1_1") (pintype "passive"))
      (node (ref "R43") (pin "2") (pinfunction "2_2") (pintype "passive"))
    )
    (net (code "151") (name "Net-(D11-A1)") (class "Default")
      (node (ref "D11") (pin "1") (pinfunction "A1_1") (pintype "passive"))
      (node (ref "R44") (pin "2") (pinfunction "2_2") (pintype "passive"))
    )
    (net (code "152") (name "Net-(D12-A1)") (class "Default")
      (node (ref "D12") (pin "1") (pinfunction "A1_1") (pintype "passive"))
      (node (ref "R45") (pin "2") (pinfunction "2_2") (pintype "passive"))
    )
    (net (code "153") (name "Net-(D13-A1)") (class "Default")
      (node (ref "D13") (pin "1") (pinfunction "A1_1") (pintype "passive"))
      (node (ref "R46") (pin "2") (pinfunction "2_2") (pintype "passive"))
    )
    (net (code "154") (name "Net-(D14-A1)") (class "Default")
      (node (ref "D14") (pin "1") (pinfunction "A1_1") (pintype "passive"))
      (node (ref "R47") (pin "2") (pinfunction "2_2") (pintype "passive"))
    )
    (net (code "155") (name "Net-(D15-A1)") (class "Default")
      (node (ref "D15") (pin "1") (pinfunction "A1_1") (pintype "passive"))
      (node (ref "R48") (pin "2") (pinfunction "2_2") (pintype "passive"))
    )
    (net (code "156") (name "Net-(D16-A1)") (class "Default")
      (node (ref "D16") (pin "1") (pinfunction "A1_1") (pintype "passive"))
      (node (ref "R49") (pin "2") (pinfunction "2_2") (pintype "passive"))
    )
    (net (code "157") (name "Net-(D17-A1)") (class "Default")
      (node (ref "D17") (pin "1") (pinfunction "A1_1") (pintype "passive"))
      (node (ref "R50") (pin "2") (pinfunction "2_2") (pintype "passive"))
    )
    (net (code "158") (name "Net-(D18-A1)") (class "Default")
      (node (ref "D18") (pin "1") (pinfunction "A1_1") (pintype "passive"))
      (node (ref "R51") (pin "2") (pinfunction "2_2") (pintype "passive"))
    )
    (net (code "159") (name "Net-(D19-A1)") (class "Default")
      (node (ref "D19") (pin "1") (pinfunction "A1_1") (pintype "passive"))
      (node (ref "R52") (pin "2") (pinfunction "2_2") (pintype "passive"))
    )
    (net (code "160") (name "Net-(D20-A1)") (class "Default")
      (node (ref "D20") (pin "1") (pinfunction "A1_1") (pintype "passive"))
      (node (ref "R53") (pin "2") (pinfunction "2_2") (pintype "passive"))
    )
    (net (code "161") (name "Net-(D21-A1)") (class "Default")
      (node (ref "D21") (pin "1") (pinfunction "A1_1") (pintype "passive"))
      (node (ref "R54") (pin "2") (pinfunction "2_2") (pintype "passive"))
    )
    (net (code "162") (name "Net-(D22-A1)") (class "Default")
      (node (ref "D22") (pin "1") (pinfunction "A1_1") (pintype "passive"))
      (node (ref "R55") (pin "2") (pinfunction "2_2") (pintype "passive"))
    )
    (net (code "163") (name "Net-(D23-A1)") (class "Default")
      (node (ref "D23") (pin "1") (pinfunction "A1_1") (pintype "passive"))
      (node (ref "R56") (pin "2") (pinfunction "2_2") (pintype "passive"))
    )
    (net (code "164") (name "Net-(D24-A1)") (class "Default")
      (node (ref "D24") (pin "1") (pinfunction "A1_1") (pintype "passive"))
      (node (ref "R57") (pin "2") (pinfunction "2_2") (pintype "passive"))
    )
    (net (code "165") (name "Net-(D25-A1)") (class "Default")
      (node (ref "D25") (pin "1") (pinfunction "A1_1") (pintype "passive"))
      (node (ref "R58") (pin "2") (pinfunction "2_2") (pintype "passive"))
    )
    (net (code "166") (name "Net-(D26-A1)") (class "Default")
      (node (ref "D26") (pin "1") (pinfunction "A1_1") (pintype "passive"))
      (node (ref "R59") (pin "2") (pinfunction "2_2") (pintype "passive"))
    )
    (net (code "167") (name "Net-(D27-A1)") (class "Default")
      (node (ref "D27") (pin "1") (pinfunction "A1_1") (pintype "passive"))
      (node (ref "R60") (pin "2") (pinfunction "2_2") (pintype "passive"))
    )
    (net (code "168") (name "Net-(D28-A1)") (class "Default")
      (node (ref "D28") (pin "1") (pinfunction "A1_1") (pintype "passive"))
      (node (ref "R61") (pin "2") (pinfunction "2_2") (pintype "passive"))
    )
    (net (code "169") (name "Net-(D29-A1)") (class "Default")
      (node (ref "D29") (pin "1") (pinfunction "A1_1") (pintype "passive"))
      (node (ref "R62") (pin "2") (pinfunction "2_2") (pintype "passive"))
    )
  )
)
